# SCH_Macropad_2023-10-24.net
KiCad netlist of a schematic drawn in EasyEDA
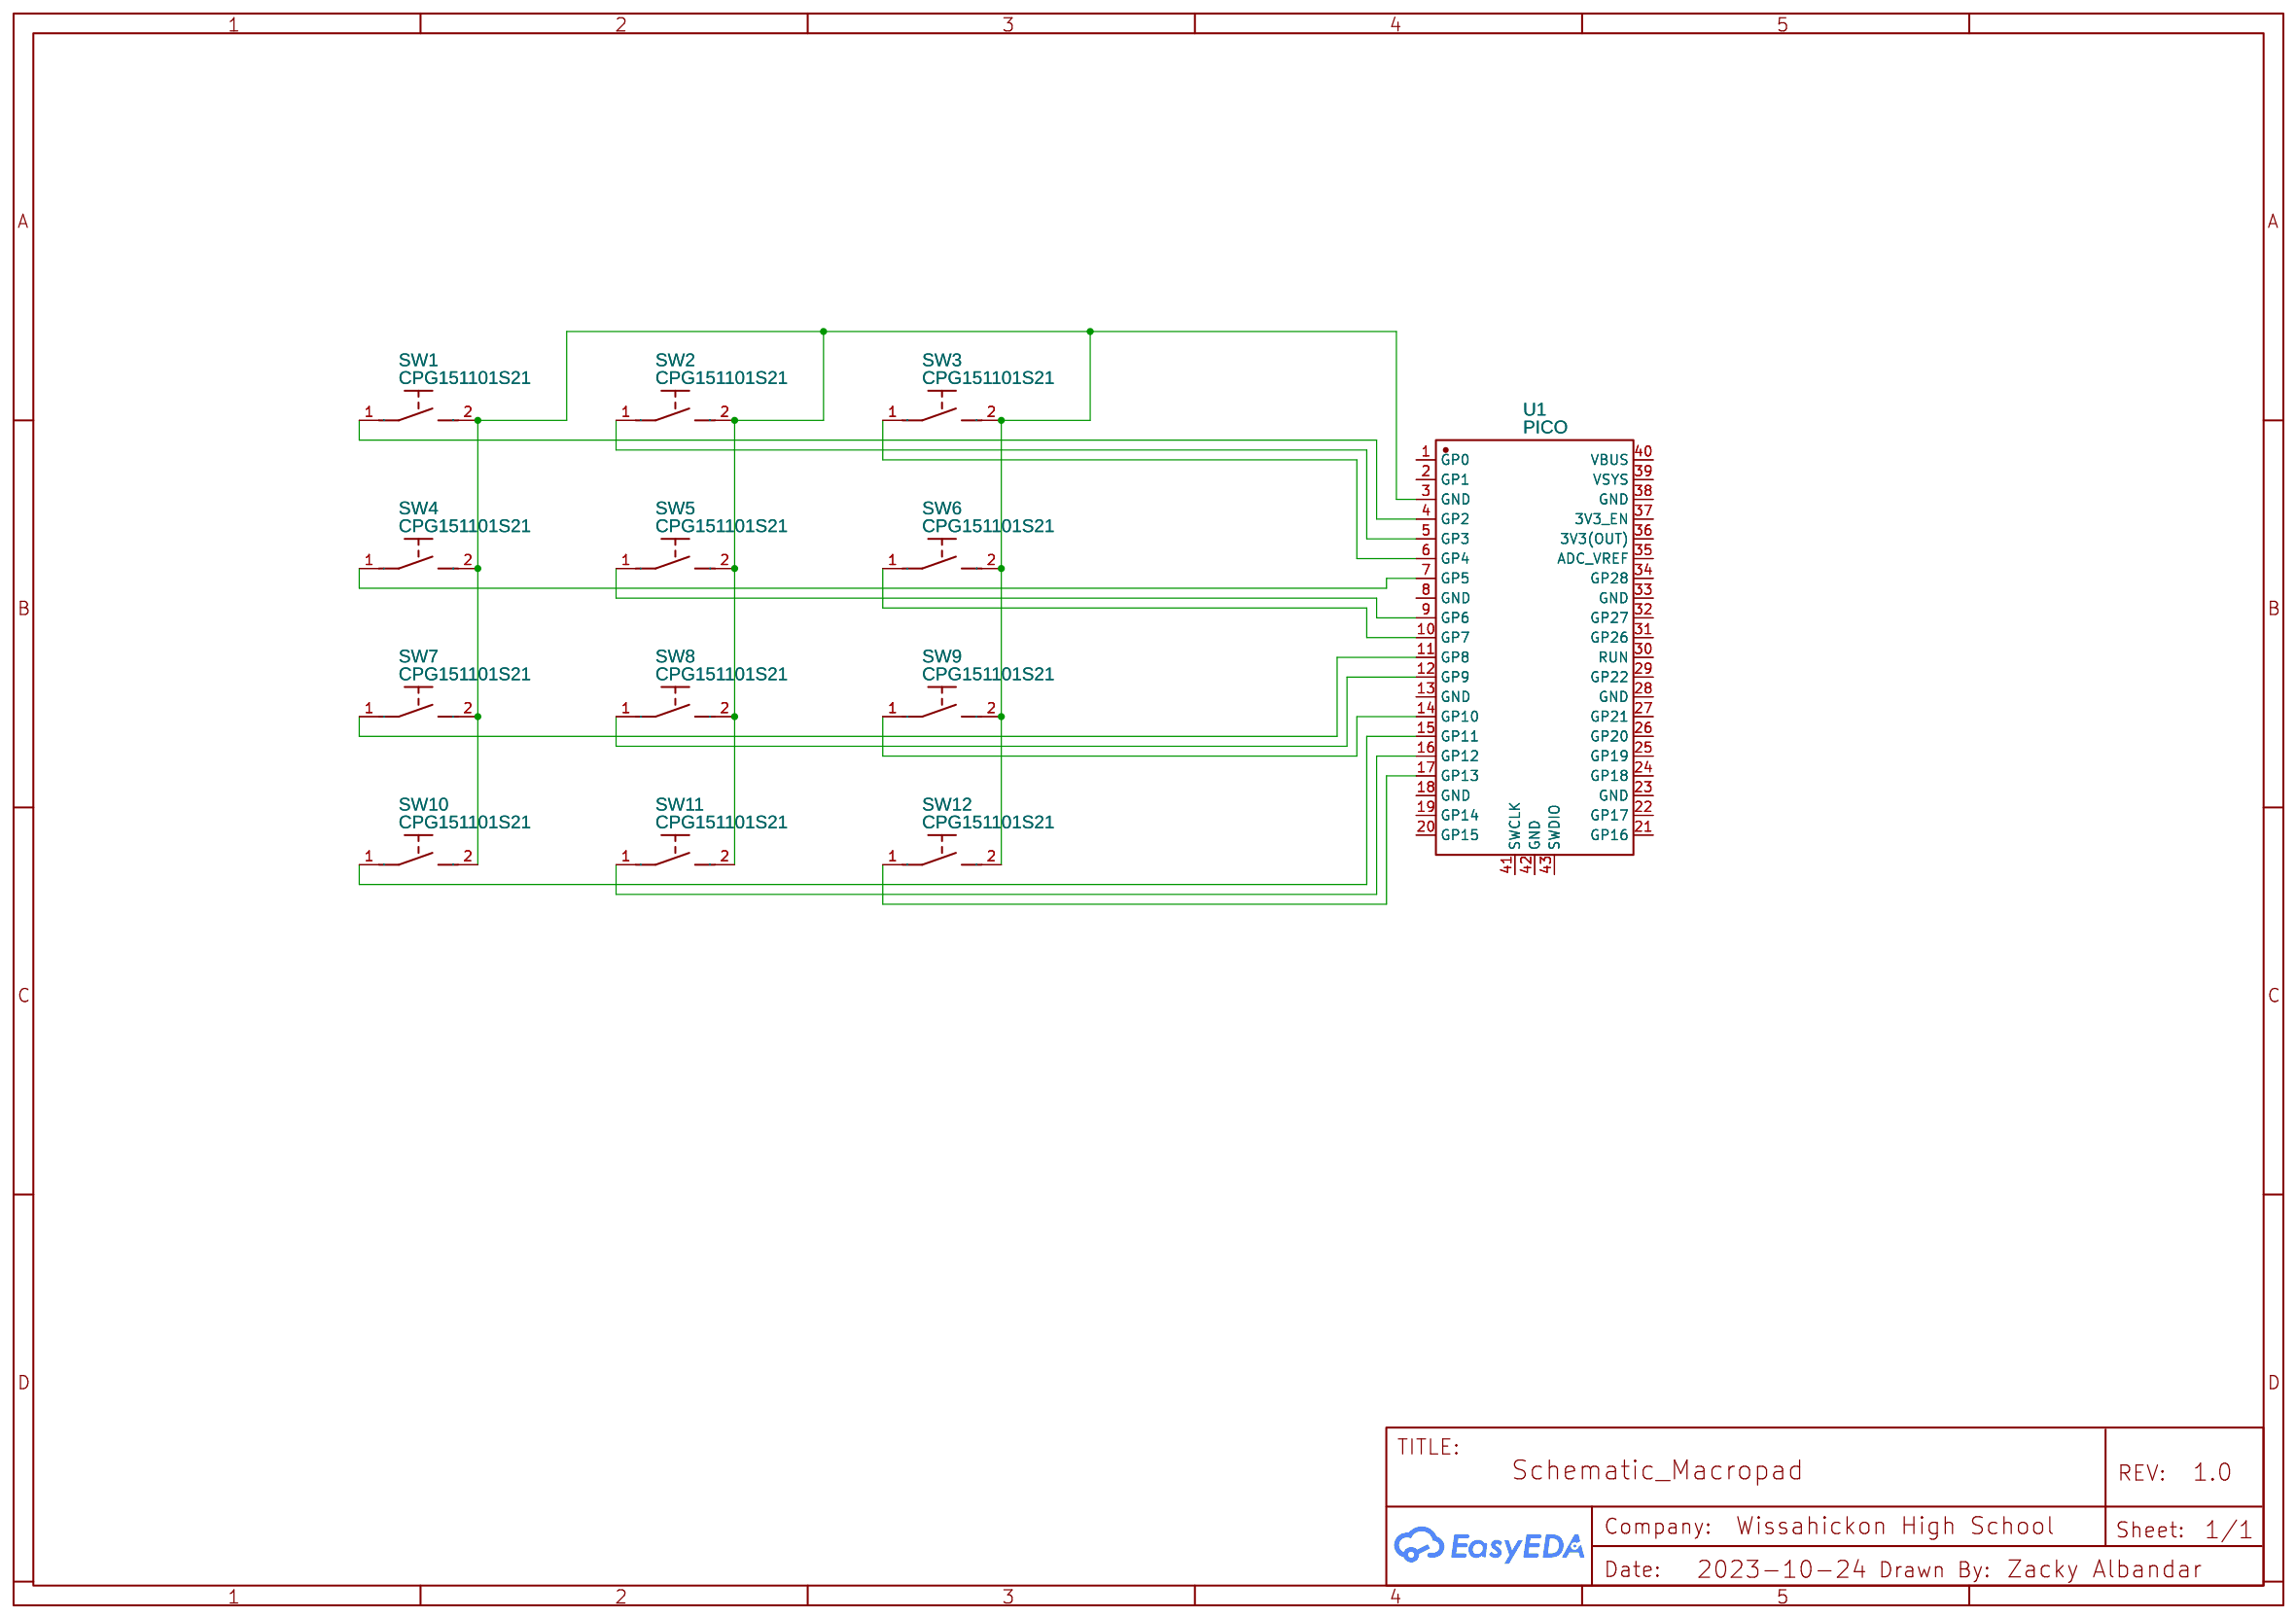
[diagram p0: schematic sheet]

(export (version "E")
  (design (tool "Eeschema 10.0.6"))
  (components
    (comp (ref "SW1")
      (value "CPG151101S21")
      (fields (field (name "Manufacturer") "Kailh(凯华)"))
      (libsource (lib "") (part "CPG151101S21"))
    )
    (comp (ref "SW2")
      (value "CPG151101S21")
      (fields (field (name "Manufacturer") "Kailh(凯华)"))
      (libsource (lib "") (part "CPG151101S21"))
    )
    (comp (ref "SW3")
      (value "CPG151101S21")
      (fields (field (name "Manufacturer") "Kailh(凯华)"))
      (libsource (lib "") (part "CPG151101S21"))
    )
    (comp (ref "SW4")
      (value "CPG151101S21")
      (fields (field (name "Manufacturer") "Kailh(凯华)"))
      (libsource (lib "") (part "CPG151101S21"))
    )
    (comp (ref "SW5")
      (value "CPG151101S21")
      (fields (field (name "Manufacturer") "Kailh(凯华)"))
      (libsource (lib "") (part "CPG151101S21"))
    )
    (comp (ref "SW6")
      (value "CPG151101S21")
      (fields (field (name "Manufacturer") "Kailh(凯华)"))
      (libsource (lib "") (part "CPG151101S21"))
    )
    (comp (ref "SW7")
      (value "CPG151101S21")
      (fields (field (name "Manufacturer") "Kailh(凯华)"))
      (libsource (lib "") (part "CPG151101S21"))
    )
    (comp (ref "SW8")
      (value "CPG151101S21")
      (fields (field (name "Manufacturer") "Kailh(凯华)"))
      (libsource (lib "") (part "CPG151101S21"))
    )
    (comp (ref "SW9")
      (value "CPG151101S21")
      (fields (field (name "Manufacturer") "Kailh(凯华)"))
      (libsource (lib "") (part "CPG151101S21"))
    )
    (comp (ref "SW10")
      (value "CPG151101S21")
      (fields (field (name "Manufacturer") "Kailh(凯华)"))
      (libsource (lib "") (part "CPG151101S21"))
    )
    (comp (ref "SW11")
      (value "CPG151101S21")
      (fields (field (name "Manufacturer") "Kailh(凯华)"))
      (libsource (lib "") (part "CPG151101S21"))
    )
    (comp (ref "SW12")
      (value "CPG151101S21")
      (fields (field (name "Manufacturer") "Kailh(凯华)"))
      (libsource (lib "") (part "CPG151101S21"))
    )
    (comp (ref "U1")
      (value "PICO")
      (fields (field (name "Manufacturer") "Raspberry Pi(树莓派)"))
      (libsource (lib "") (part "PICO"))
    )
  )
  (nets
    (net (code "1") (name "Net-(SW1-Pad2)") (class "Default")
      (node (ref "SW1") (pin "2") (pinfunction "2_2") (pintype "unspecified"))
      (node (ref "SW10") (pin "2") (pinfunction "2_2") (pintype "unspecified"))
      (node (ref "SW11") (pin "2") (pinfunction "2_2") (pintype "unspecified"))
      (node (ref "SW12") (pin "2") (pinfunction "2_2") (pintype "unspecified"))
      (node (ref "SW2") (pin "2") (pinfunction "2_2") (pintype "unspecified"))
      (node (ref "SW3") (pin "2") (pinfunction "2_2") (pintype "unspecified"))
      (node (ref "SW4") (pin "2") (pinfunction "2_2") (pintype "unspecified"))
      (node (ref "SW5") (pin "2") (pinfunction "2_2") (pintype "unspecified"))
      (node (ref "SW6") (pin "2") (pinfunction "2_2") (pintype "unspecified"))
      (node (ref "SW7") (pin "2") (pinfunction "2_2") (pintype "unspecified"))
      (node (ref "SW8") (pin "2") (pinfunction "2_2") (pintype "unspecified"))
      (node (ref "SW9") (pin "2") (pinfunction "2_2") (pintype "unspecified"))
      (node (ref "U1") (pin "3") (pinfunction "GND_3") (pintype "unspecified"))
    )
    (net (code "2") (name "Net-(U1-GP2)") (class "Default")
      (node (ref "SW1") (pin "1") (pinfunction "1_1") (pintype "unspecified"))
      (node (ref "U1") (pin "4") (pinfunction "GP2_4") (pintype "unspecified"))
    )
    (net (code "3") (name "Net-(U1-GP3)") (class "Default")
      (node (ref "SW2") (pin "1") (pinfunction "1_1") (pintype "unspecified"))
      (node (ref "U1") (pin "5") (pinfunction "GP3_5") (pintype "unspecified"))
    )
    (net (code "4") (name "Net-(U1-GP4)") (class "Default")
      (node (ref "SW3") (pin "1") (pinfunction "1_1") (pintype "unspecified"))
      (node (ref "U1") (pin "6") (pinfunction "GP4_6") (pintype "unspecified"))
    )
    (net (code "5") (name "Net-(U1-GP5)") (class "Default")
      (node (ref "SW4") (pin "1") (pinfunction "1_1") (pintype "unspecified"))
      (node (ref "U1") (pin "7") (pinfunction "GP5_7") (pintype "unspecified"))
    )
    (net (code "6") (name "Net-(U1-GP6)") (class "Default")
      (node (ref "SW5") (pin "1") (pinfunction "1_1") (pintype "unspecified"))
      (node (ref "U1") (pin "9") (pinfunction "GP6_9") (pintype "unspecified"))
    )
    (net (code "7") (name "Net-(U1-GP7)") (class "Default")
      (node (ref "SW6") (pin "1") (pinfunction "1_1") (pintype "unspecified"))
      (node (ref "U1") (pin "10") (pinfunction "GP7_10") (pintype "unspecified"))
    )
    (net (code "8") (name "Net-(U1-GP8)") (class "Default")
      (node (ref "SW7") (pin "1") (pinfunction "1_1") (pintype "unspecified"))
      (node (ref "U1") (pin "11") (pinfunction "GP8_11") (pintype "unspecified"))
    )
    (net (code "9") (name "Net-(U1-GP9)") (class "Default")
      (node (ref "SW8") (pin "1") (pinfunction "1_1") (pintype "unspecified"))
      (node (ref "U1") (pin "12") (pinfunction "GP9_12") (pintype "unspecified"))
    )
    (net (code "10") (name "Net-(U1-GP10)") (class "Default")
      (node (ref "SW9") (pin "1") (pinfunction "1_1") (pintype "unspecified"))
      (node (ref "U1") (pin "14") (pinfunction "GP10_14") (pintype "unspecified"))
    )
    (net (code "11") (name "Net-(U1-GP11)") (class "Default")
      (node (ref "SW10") (pin "1") (pinfunction "1_1") (pintype "unspecified"))
      (node (ref "U1") (pin "15") (pinfunction "GP11_15") (pintype "unspecified"))
    )
    (net (code "12") (name "Net-(U1-GP12)") (class "Default")
      (node (ref "SW11") (pin "1") (pinfunction "1_1") (pintype "unspecified"))
      (node (ref "U1") (pin "16") (pinfunction "GP12_16") (pintype "unspecified"))
    )
    (net (code "13") (name "Net-(U1-GP13)") (class "Default")
      (node (ref "SW12") (pin "1") (pinfunction "1_1") (pintype "unspecified"))
      (node (ref "U1") (pin "17") (pinfunction "GP13_17") (pintype "unspecified"))
    )
    (net (code "14") (name "unconnected-(U1-3V3(OUT)-Pad36)") (class "Default")
      (node (ref "U1") (pin "36") (pinfunction "3V3(OUT)_36") (pintype "unspecified"))
    )
    (net (code "15") (name "unconnected-(U1-3V3_EN-Pad37)") (class "Default")
      (node (ref "U1") (pin "37") (pinfunction "3V3_EN_37") (pintype "unspecified"))
    )
    (net (code "16") (name "unconnected-(U1-ADC_VREF-Pad35)") (class "Default")
      (node (ref "U1") (pin "35") (pinfunction "ADC_VREF_35") (pintype "unspecified"))
    )
    (net (code "17") (name "unconnected-(U1-GND-Pad8)") (class "Default")
      (node (ref "U1") (pin "8") (pinfunction "GND_8") (pintype "unspecified"))
    )
    (net (code "18") (name "unconnected-(U1-GND-Pad13)") (class "Default")
      (node (ref "U1") (pin "13") (pinfunction "GND_13") (pintype "unspecified"))
    )
    (net (code "19") (name "unconnected-(U1-GND-Pad18)") (class "Default")
      (node (ref "U1") (pin "18") (pinfunction "GND_18") (pintype "unspecified"))
    )
    (net (code "20") (name "unconnected-(U1-GND-Pad23)") (class "Default")
      (node (ref "U1") (pin "23") (pinfunction "GND_23") (pintype "unspecified"))
    )
    (net (code "21") (name "unconnected-(U1-GND-Pad28)") (class "Default")
      (node (ref "U1") (pin "28") (pinfunction "GND_28") (pintype "unspecified"))
    )
    (net (code "22") (name "unconnected-(U1-GND-Pad33)") (class "Default")
      (node (ref "U1") (pin "33") (pinfunction "GND_33") (pintype "unspecified"))
    )
    (net (code "23") (name "unconnected-(U1-GND-Pad38)") (class "Default")
      (node (ref "U1") (pin "38") (pinfunction "GND_38") (pintype "unspecified"))
    )
    (net (code "24") (name "unconnected-(U1-GND-Pad42)") (class "Default")
      (node (ref "U1") (pin "42") (pinfunction "GND_42") (pintype "unspecified"))
    )
    (net (code "25") (name "unconnected-(U1-GP0-Pad1)") (class "Default")
      (node (ref "U1") (pin "1") (pinfunction "GP0_1") (pintype "unspecified"))
    )
    (net (code "26") (name "unconnected-(U1-GP1-Pad2)") (class "Default")
      (node (ref "U1") (pin "2") (pinfunction "GP1_2") (pintype "unspecified"))
    )
    (net (code "27") (name "unconnected-(U1-GP14-Pad19)") (class "Default")
      (node (ref "U1") (pin "19") (pinfunction "GP14_19") (pintype "unspecified"))
    )
    (net (code "28") (name "unconnected-(U1-GP15-Pad20)") (class "Default")
      (node (ref "U1") (pin "20") (pinfunction "GP15_20") (pintype "unspecified"))
    )
    (net (code "29") (name "unconnected-(U1-GP16-Pad21)") (class "Default")
      (node (ref "U1") (pin "21") (pinfunction "GP16_21") (pintype "unspecified"))
    )
    (net (code "30") (name "unconnected-(U1-GP17-Pad22)") (class "Default")
      (node (ref "U1") (pin "22") (pinfunction "GP17_22") (pintype "unspecified"))
    )
    (net (code "31") (name "unconnected-(U1-GP18-Pad24)") (class "Default")
      (node (ref "U1") (pin "24") (pinfunction "GP18_24") (pintype "unspecified"))
    )
    (net (code "32") (name "unconnected-(U1-GP19-Pad25)") (class "Default")
      (node (ref "U1") (pin "25") (pinfunction "GP19_25") (pintype "unspecified"))
    )
    (net (code "33") (name "unconnected-(U1-GP20-Pad26)") (class "Default")
      (node (ref "U1") (pin "26") (pinfunction "GP20_26") (pintype "unspecified"))
    )
    (net (code "34") (name "unconnected-(U1-GP21-Pad27)") (class "Default")
      (node (ref "U1") (pin "27") (pinfunction "GP21_27") (pintype "unspecified"))
    )
    (net (code "35") (name "unconnected-(U1-GP22-Pad29)") (class "Default")
      (node (ref "U1") (pin "29") (pinfunction "GP22_29") (pintype "unspecified"))
    )
    (net (code "36") (name "unconnected-(U1-GP26-Pad31)") (class "Default")
      (node (ref "U1") (pin "31") (pinfunction "GP26_31") (pintype "unspecified"))
    )
    (net (code "37") (name "unconnected-(U1-GP27-Pad32)") (class "Default")
      (node (ref "U1") (pin "32") (pinfunction "GP27_32") (pintype "unspecified"))
    )
    (net (code "38") (name "unconnected-(U1-GP28-Pad34)") (class "Default")
      (node (ref "U1") (pin "34") (pinfunction "GP28_34") (pintype "unspecified"))
    )
    (net (code "39") (name "unconnected-(U1-RUN-Pad30)") (class "Default")
      (node (ref "U1") (pin "30") (pinfunction "RUN_30") (pintype "unspecified"))
    )
    (net (code "40") (name "unconnected-(U1-SWCLK-Pad41)") (class "Default")
      (node (ref "U1") (pin "41") (pinfunction "SWCLK_41") (pintype "unspecified"))
    )
    (net (code "41") (name "unconnected-(U1-SWDIO-Pad43)") (class "Default")
      (node (ref "U1") (pin "43") (pinfunction "SWDIO_43") (pintype "unspecified"))
    )
    (net (code "42") (name "unconnected-(U1-VBUS-Pad40)") (class "Default")
      (node (ref "U1") (pin "40") (pinfunction "VBUS_40") (pintype "unspecified"))
    )
    (net (code "43") (name "unconnected-(U1-VSYS-Pad39)") (class "Default")
      (node (ref "U1") (pin "39") (pinfunction "VSYS_39") (pintype "unspecified"))
    )
  )
)
